# EurocardPowerSupply_mods.net
KiCad netlist of a schematic drawn in EAGLE
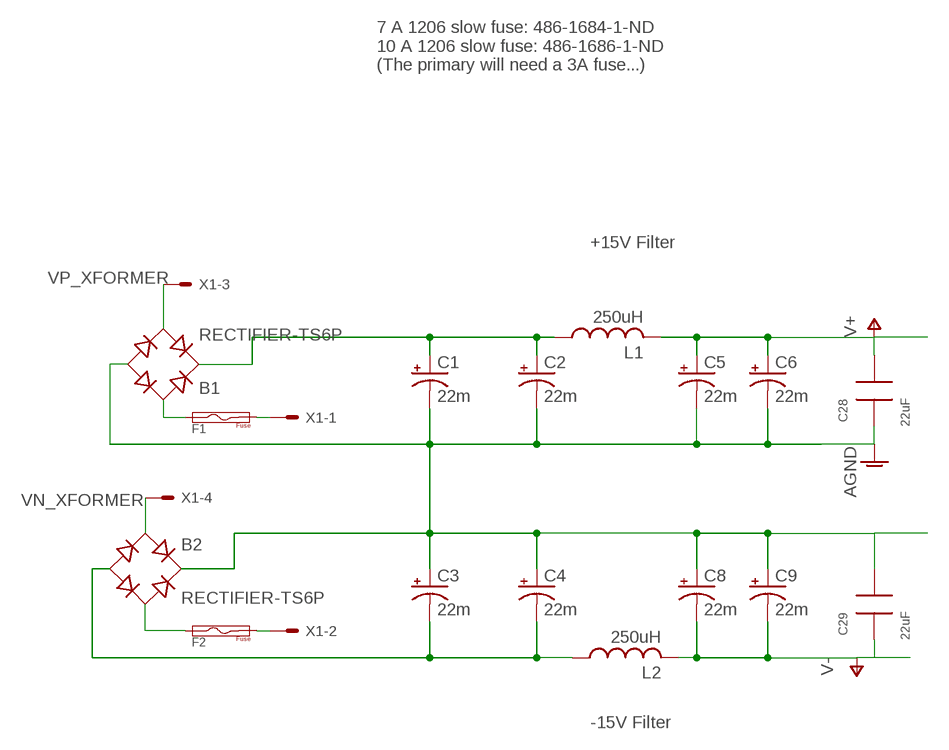
[diagram p0: schematic, sheet 1]
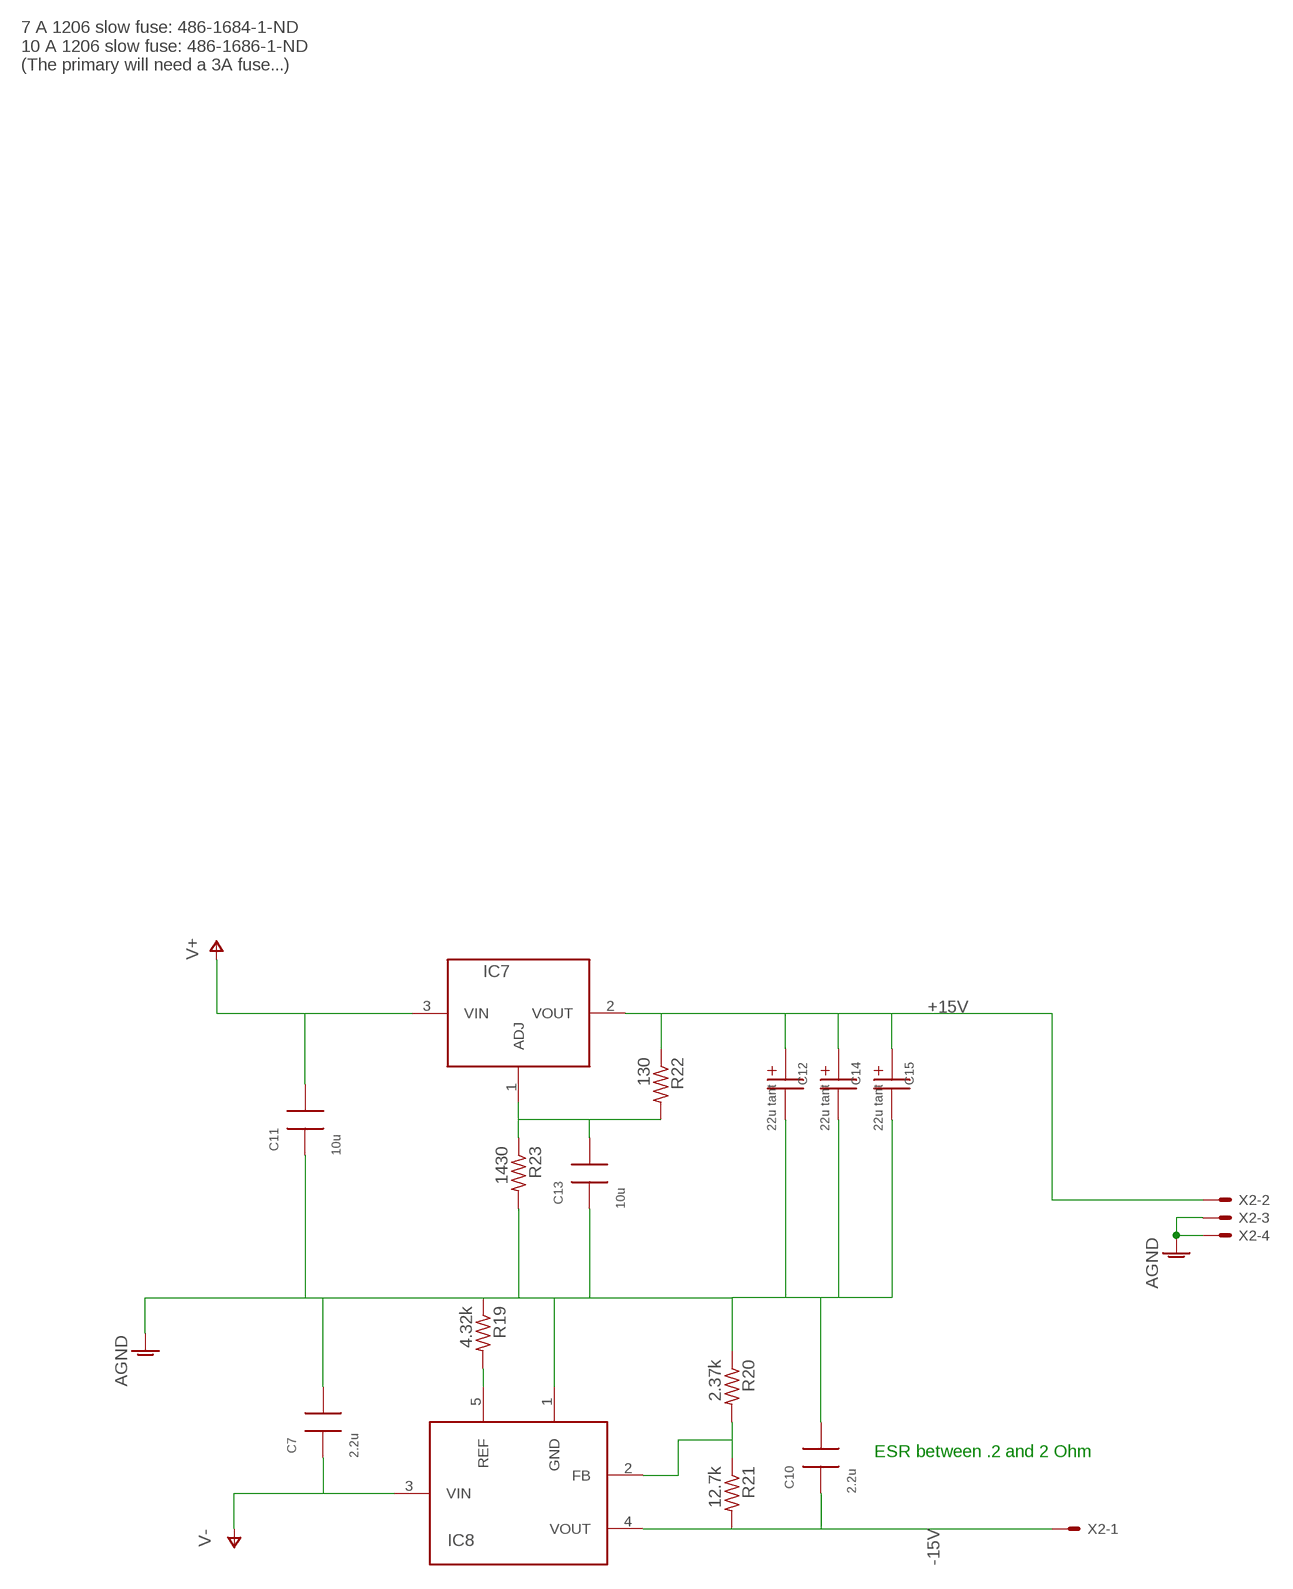
[diagram p1: schematic, sheet 2]
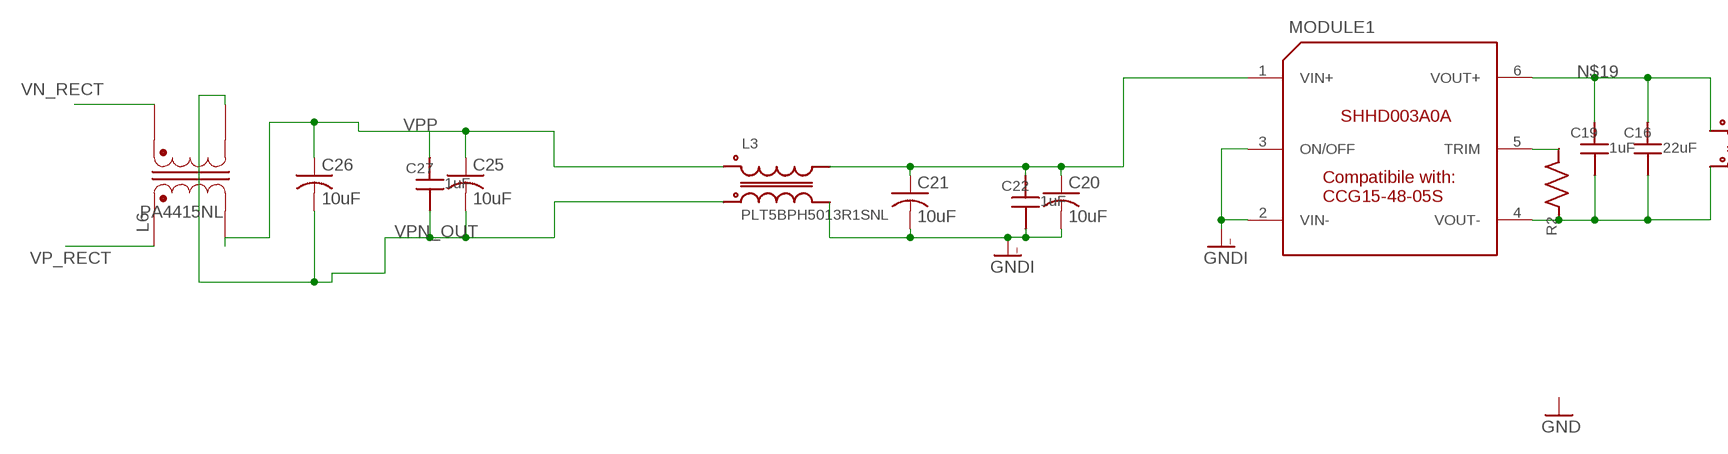
[diagram p2: schematic, sheet 3, part 1 of 2]
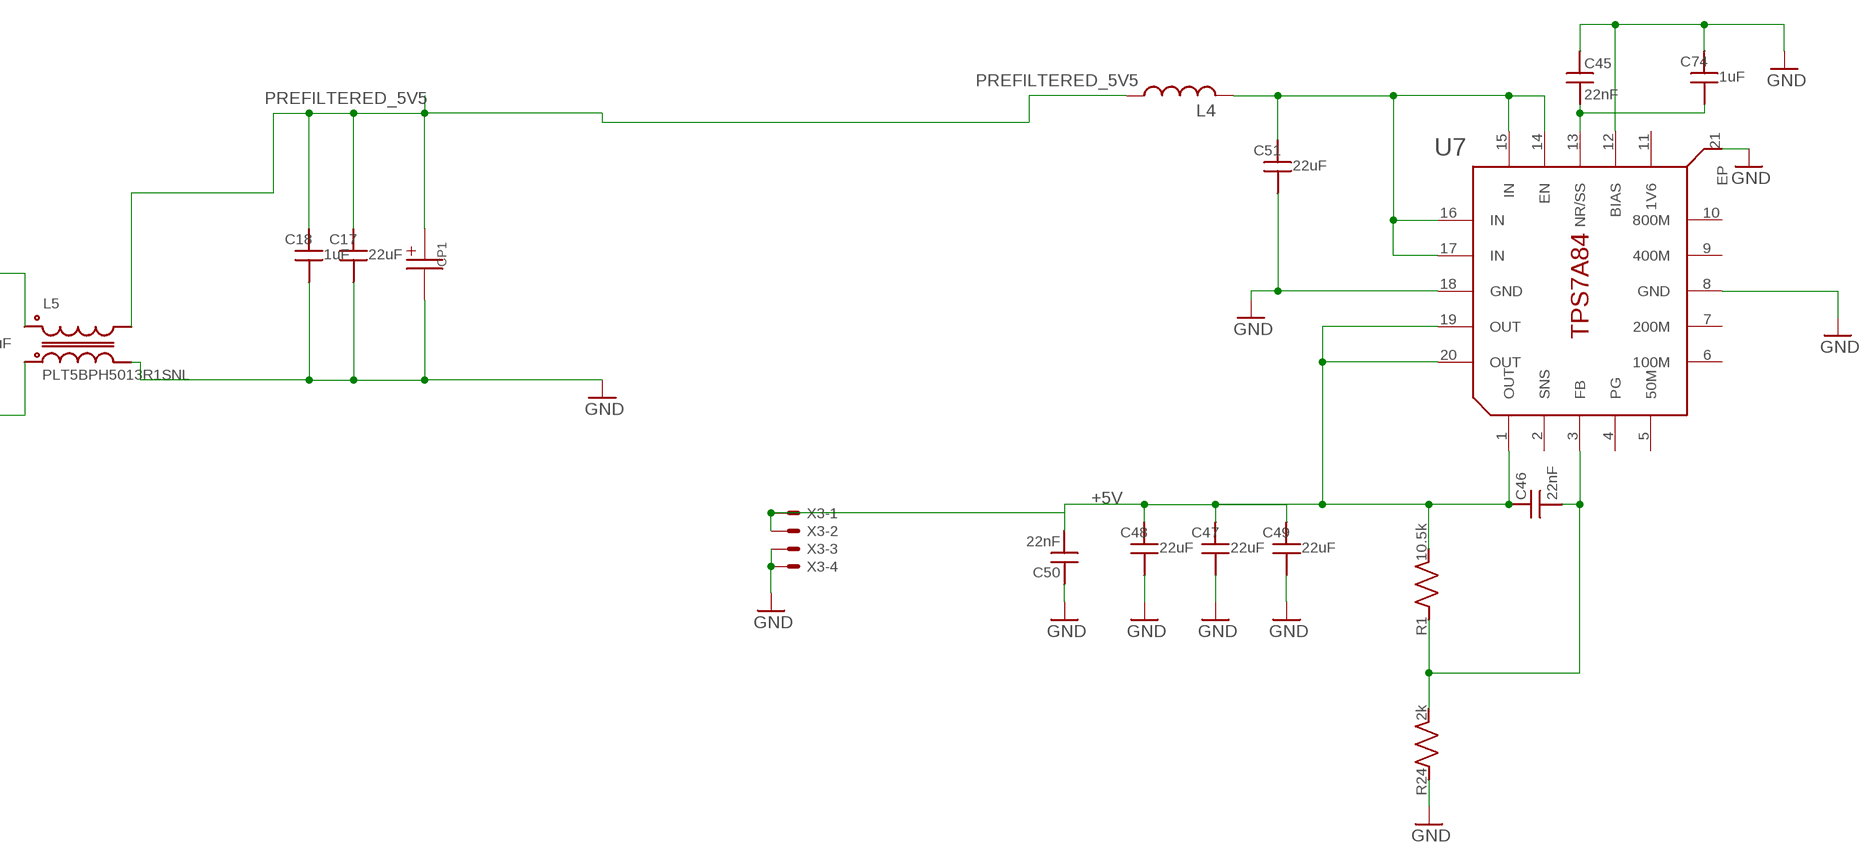
[diagram p3: schematic, sheet 3, part 2 of 2]

(export (version "E")
  (design (tool "Eeschema 10.0.6"))
  (components
    (comp (ref "C7")
      (value "2.2u")
      (footprint "eagle-import:1206")
      (libsource (lib "eagle-import") (part "CAP1206"))
    )
    (comp (ref "C10")
      (value "2.2u")
      (footprint "eagle-import:1206")
      (libsource (lib "eagle-import") (part "CAP1206"))
    )
    (comp (ref "C11")
      (value "10u")
      (footprint "eagle-import:1206")
      (libsource (lib "eagle-import") (part "CAP1206"))
    )
    (comp (ref "C12")
      (value "22u tant")
      (footprint "eagle-import:1206P")
      (libsource (lib "eagle-import") (part "rlc-jqi_CAP-POL1206"))
    )
    (comp (ref "C13")
      (value "10u")
      (footprint "eagle-import:1206")
      (libsource (lib "eagle-import") (part "CAP1206"))
    )
    (comp (ref "C14")
      (value "22u tant")
      (footprint "eagle-import:1206P")
      (libsource (lib "eagle-import") (part "rlc-jqi_CAP-POL1206"))
    )
    (comp (ref "C15")
      (value "22u tant")
      (footprint "eagle-import:1206P")
      (libsource (lib "eagle-import") (part "rlc-jqi_CAP-POL1206"))
    )
    (comp (ref "IC7")
      (value "LM1084TO220")
      (footprint "eagle-import:T03B")
      (libsource (lib "eagle-import") (part "LM1084TO220"))
    )
    (comp (ref "IC8")
      (value "LT1185TO220/INLINE")
      (footprint "eagle-import:T05A")
      (libsource (lib "eagle-import") (part "LT1185TO220/INLINE"))
    )
    (comp (ref "R19")
      (value "4.32k")
      (footprint "eagle-import:R1206")
      (libsource (lib "eagle-import") (part "R-US_R1206"))
    )
    (comp (ref "R20")
      (value "2.37k")
      (footprint "eagle-import:R1206")
      (libsource (lib "eagle-import") (part "R-US_R1206"))
    )
    (comp (ref "R21")
      (value "12.7k")
      (footprint "eagle-import:R1206")
      (libsource (lib "eagle-import") (part "R-US_R1206"))
    )
    (comp (ref "R22")
      (value "130")
      (footprint "eagle-import:R1206")
      (libsource (lib "eagle-import") (part "R-US_R1206"))
    )
    (comp (ref "R23")
      (value "1430")
      (footprint "eagle-import:R1206")
      (libsource (lib "eagle-import") (part "R-US_R1206"))
    )
    (comp (ref "X2")
      (value "5566-4")
      (footprint "eagle-import:5566-4")
      (libsource (lib "eagle-import") (part "5566-4"))
    )
    (comp (ref "B1")
      (value "RECTIFIER-TS6P")
      (footprint "eagle-import:TS6P")
      (libsource (lib "eagle-import") (part "RECTIFIER-TS6P"))
    )
    (comp (ref "B2")
      (value "RECTIFIER-TS6P")
      (footprint "eagle-import:TS6P")
      (libsource (lib "eagle-import") (part "RECTIFIER-TS6P"))
    )
    (comp (ref "C1")
      (value "22m")
      (footprint "eagle-import:EB35D")
      (libsource (lib "eagle-import") (part "CPOL-USEB35D"))
    )
    (comp (ref "C2")
      (value "22m")
      (footprint "eagle-import:EB35D")
      (libsource (lib "eagle-import") (part "CPOL-USEB35D"))
    )
    (comp (ref "C3")
      (value "22m")
      (footprint "eagle-import:EB35D")
      (libsource (lib "eagle-import") (part "CPOL-USEB35D"))
    )
    (comp (ref "C4")
      (value "22m")
      (footprint "eagle-import:EB35D")
      (libsource (lib "eagle-import") (part "CPOL-USEB35D"))
    )
    (comp (ref "C5")
      (value "22m")
      (footprint "eagle-import:EB35D")
      (libsource (lib "eagle-import") (part "CPOL-USEB35D"))
    )
    (comp (ref "C6")
      (value "22m")
      (footprint "eagle-import:EB35D")
      (libsource (lib "eagle-import") (part "CPOL-USEB35D"))
    )
    (comp (ref "C8")
      (value "22m")
      (footprint "eagle-import:EB35D")
      (libsource (lib "eagle-import") (part "CPOL-USEB35D"))
    )
    (comp (ref "C9")
      (value "22m")
      (footprint "eagle-import:EB35D")
      (libsource (lib "eagle-import") (part "CPOL-USEB35D"))
    )
    (comp (ref "C28")
      (value "22uF")
      (footprint "eagle-import:1206")
      (libsource (lib "eagle-import") (part "CAP1206"))
    )
    (comp (ref "C29")
      (value "22uF")
      (footprint "eagle-import:1206")
      (libsource (lib "eagle-import") (part "CAP1206"))
    )
    (comp (ref "F1")
      (value "FUSE1206")
      (footprint "eagle-import:FUSE1206")
      (libsource (lib "eagle-import") (part "FUSE1206"))
    )
    (comp (ref "F2")
      (value "FUSE1206")
      (footprint "eagle-import:FUSE1206")
      (libsource (lib "eagle-import") (part "FUSE1206"))
    )
    (comp (ref "L1")
      (value "250uH")
      (footprint "eagle-import:5721-RC")
      (libsource (lib "eagle-import") (part "INDUCTOR5721-RC"))
    )
    (comp (ref "L2")
      (value "250uH")
      (footprint "eagle-import:5721-RC")
      (libsource (lib "eagle-import") (part "INDUCTOR5721-RC"))
    )
    (comp (ref "X1")
      (value "5566-4")
      (footprint "eagle-import:5566-4")
      (libsource (lib "eagle-import") (part "5566-4"))
    )
    (comp (ref "C16")
      (value "22uF")
      (footprint "eagle-import:C_MLCC_0805")
      (libsource (lib "eagle-import") (part "C_MLCC_SMDCMLCC_0805"))
    )
    (comp (ref "C17")
      (value "22uF")
      (footprint "eagle-import:C_MLCC_0805")
      (libsource (lib "eagle-import") (part "C_MLCC_SMDCMLCC_0805"))
    )
    (comp (ref "C18")
      (value "1uF")
      (footprint "eagle-import:C_MLCC_0805")
      (libsource (lib "eagle-import") (part "C_MLCC_SMDCMLCC_0805"))
    )
    (comp (ref "C19")
      (value "1uF")
      (footprint "eagle-import:C_MLCC_0805")
      (libsource (lib "eagle-import") (part "C_MLCC_SMDCMLCC_0805"))
    )
    (comp (ref "C20")
      (value "10uF")
      (footprint "eagle-import:C2220K")
      (libsource (lib "eagle-import") (part "C-USC2220K"))
    )
    (comp (ref "C21")
      (value "10uF")
      (footprint "eagle-import:C2220K")
      (libsource (lib "eagle-import") (part "C-USC2220K"))
    )
    (comp (ref "C22")
      (value "1uF")
      (footprint "eagle-import:C_MLCC_0805")
      (libsource (lib "eagle-import") (part "C_MLCC_SMDCMLCC_0805"))
    )
    (comp (ref "C25")
      (value "10uF")
      (footprint "eagle-import:C2220K")
      (libsource (lib "eagle-import") (part "C-USC2220K"))
    )
    (comp (ref "C26")
      (value "10uF")
      (footprint "eagle-import:C2220K")
      (libsource (lib "eagle-import") (part "C-USC2220K"))
    )
    (comp (ref "C27")
      (value "1uF")
      (footprint "eagle-import:C_MLCC_0805")
      (libsource (lib "eagle-import") (part "C_MLCC_SMDCMLCC_0805"))
    )
    (comp (ref "C45")
      (value "22nF")
      (footprint "eagle-import:C_MLCC_0306")
      (libsource (lib "eagle-import") (part "C_MLCC_SMDCMLCC_0306"))
    )
    (comp (ref "C46")
      (value "22nF")
      (footprint "eagle-import:C_MLCC_0306")
      (libsource (lib "eagle-import") (part "C_MLCC_SMDCMLCC_0306"))
    )
    (comp (ref "C47")
      (value "22uF")
      (footprint "eagle-import:C_MLCC_0805")
      (libsource (lib "eagle-import") (part "C_MLCC_SMDCMLCC_0805"))
    )
    (comp (ref "C48")
      (value "22uF")
      (footprint "eagle-import:C_MLCC_0805")
      (libsource (lib "eagle-import") (part "C_MLCC_SMDCMLCC_0805"))
    )
    (comp (ref "C49")
      (value "22uF")
      (footprint "eagle-import:C_MLCC_0805")
      (libsource (lib "eagle-import") (part "C_MLCC_SMDCMLCC_0805"))
    )
    (comp (ref "C50")
      (value "22nF")
      (footprint "eagle-import:C_MLCC_0306")
      (libsource (lib "eagle-import") (part "C_MLCC_SMDCMLCC_0306"))
    )
    (comp (ref "C51")
      (value "22uF")
      (footprint "eagle-import:C_MLCC_0805")
      (libsource (lib "eagle-import") (part "C_MLCC_SMDCMLCC_0805"))
    )
    (comp (ref "C74")
      (value "1uF")
      (footprint "eagle-import:C_MLCC_0805")
      (libsource (lib "eagle-import") (part "C_MLCC_SMDCMLCC_0805"))
    )
    (comp (ref "CP1")
      (value "CAP-POLPANASONIC_F")
      (footprint "eagle-import:PANASONIC_F")
      (libsource (lib "eagle-import") (part "CAP-POLPANASONIC_F"))
    )
    (comp (ref "L3")
      (value "PLT5BPH5013R1SNL")
      (footprint "eagle-import:MURATA_CM_CHOKE_PLT5BPH_SERIES")
      (libsource (lib "eagle-import") (part "MURATA_CM_COIL_SERIES_PLT5BPH"))
    )
    (comp (ref "L4")
      (value "MURATA_NFZ5BBW100LN10L")
      (footprint "eagle-import:MURATA_1MHZ_3A_FERRITE")
      (libsource (lib "eagle-import") (part "MURATA_NFZ5BBW100LN10L"))
    )
    (comp (ref "L5")
      (value "PLT5BPH5013R1SNL")
      (footprint "eagle-import:MURATA_CM_CHOKE_PLT5BPH_SERIES")
      (libsource (lib "eagle-import") (part "MURATA_CM_COIL_SERIES_PLT5BPH"))
    )
    (comp (ref "L6")
      (value "PA4415NL")
      (footprint "eagle-import:PA4415NL")
      (libsource (lib "eagle-import") (part "PA4415NL"))
    )
    (comp (ref "MODULE1")
      (value "GE_SHHD003A0A")
      (footprint "eagle-import:GE_SHHD003A0A_THROUGH_HOLE")
      (libsource (lib "eagle-import") (part "GE_SHHD003A0A"))
    )
    (comp (ref "R1")
      (value "10.5k")
      (footprint "eagle-import:R_0805")
      (libsource (lib "eagle-import") (part "R_SMDR0805"))
    )
    (comp (ref "R2")
      (value "R_SMDR0805")
      (footprint "eagle-import:R_0805")
      (libsource (lib "eagle-import") (part "R_SMDR0805"))
    )
    (comp (ref "R24")
      (value "2k")
      (footprint "eagle-import:R_0805")
      (libsource (lib "eagle-import") (part "R_SMDR0805"))
    )
    (comp (ref "U7")
      (value "TEXAS_INSTRUMENTS_TPS7A84")
      (footprint "eagle-import:S-PVQFN-N20")
      (libsource (lib "eagle-import") (part "TEXAS_INSTRUMENTS_TPS7A84"))
    )
    (comp (ref "X3")
      (value "5566-4")
      (footprint "eagle-import:5566-4")
      (libsource (lib "eagle-import") (part "5566-4"))
    )
  )
  (nets
    (net (code "1") (name "+5V") (class "Default")
      (node (ref "C46") (pin "P$1") (pinfunction "1_P$1") (pintype "passive"))
      (node (ref "C47") (pin "P$1") (pinfunction "1_P$1") (pintype "passive"))
      (node (ref "C48") (pin "P$1") (pinfunction "1_P$1") (pintype "passive"))
      (node (ref "C49") (pin "P$1") (pinfunction "1_P$1") (pintype "passive"))
      (node (ref "C50") (pin "P$2") (pinfunction "2_P$2") (pintype "passive"))
      (node (ref "R1") (pin "P$2") (pinfunction "2_P$2") (pintype "passive"))
      (node (ref "U7") (pin "1") (pinfunction "OUT_1") (pintype "bidirectional"))
      (node (ref "U7") (pin "19") (pinfunction "OUT_19") (pintype "bidirectional"))
      (node (ref "U7") (pin "20") (pinfunction "OUT_20") (pintype "bidirectional"))
      (node (ref "X3") (pin "1") (pinfunction "S_1") (pintype "passive"))
      (node (ref "X3") (pin "2") (pinfunction "S_2") (pintype "passive"))
    )
    (net (code "2") (name "+15V") (class "Default")
      (node (ref "C12") (pin "1") (pinfunction "P$1_1") (pintype "passive"))
      (node (ref "C14") (pin "1") (pinfunction "P$1_1") (pintype "passive"))
      (node (ref "C15") (pin "1") (pinfunction "P$1_1") (pintype "passive"))
      (node (ref "IC7") (pin "2") (pinfunction "VOUT_2") (pintype "bidirectional"))
      (node (ref "R22") (pin "1") (pinfunction "1_1") (pintype "passive"))
      (node (ref "X2") (pin "2") (pinfunction "S_2") (pintype "passive"))
    )
    (net (code "3") (name "-15V") (class "Default")
      (node (ref "C10") (pin "1") (pinfunction "P$1_1") (pintype "passive"))
      (node (ref "IC8") (pin "4") (pinfunction "VOUT_4") (pintype "bidirectional"))
      (node (ref "R21") (pin "2") (pinfunction "2_2") (pintype "passive"))
      (node (ref "X2") (pin "1") (pinfunction "S_1") (pintype "passive"))
    )
    (net (code "4") (name "AGND") (class "Default")
      (node (ref "B1") (pin "-") (pinfunction "-_-") (pintype "passive"))
      (node (ref "B2") (pin "+") (pinfunction "+_+") (pintype "passive"))
      (node (ref "C1") (pin "-") (pinfunction "-_-") (pintype "passive"))
      (node (ref "C10") (pin "2") (pinfunction "P$2_2") (pintype "passive"))
      (node (ref "C11") (pin "1") (pinfunction "P$1_1") (pintype "passive"))
      (node (ref "C12") (pin "2") (pinfunction "P$2_2") (pintype "passive"))
      (node (ref "C13") (pin "1") (pinfunction "P$1_1") (pintype "passive"))
      (node (ref "C14") (pin "2") (pinfunction "P$2_2") (pintype "passive"))
      (node (ref "C15") (pin "2") (pinfunction "P$2_2") (pintype "passive"))
      (node (ref "C2") (pin "-") (pinfunction "-_-") (pintype "passive"))
      (node (ref "C28") (pin "1") (pinfunction "P$1_1") (pintype "passive"))
      (node (ref "C29") (pin "2") (pinfunction "P$2_2") (pintype "passive"))
      (node (ref "C3") (pin "+") (pinfunction "+_+") (pintype "passive"))
      (node (ref "C4") (pin "+") (pinfunction "+_+") (pintype "passive"))
      (node (ref "C5") (pin "-") (pinfunction "-_-") (pintype "passive"))
      (node (ref "C6") (pin "-") (pinfunction "-_-") (pintype "passive"))
      (node (ref "C7") (pin "2") (pinfunction "P$2_2") (pintype "passive"))
      (node (ref "C8") (pin "+") (pinfunction "+_+") (pintype "passive"))
      (node (ref "C9") (pin "+") (pinfunction "+_+") (pintype "passive"))
      (node (ref "IC8") (pin "1") (pinfunction "GND_1") (pintype "bidirectional"))
      (node (ref "R19") (pin "1") (pinfunction "1_1") (pintype "passive"))
      (node (ref "R20") (pin "1") (pinfunction "1_1") (pintype "passive"))
      (node (ref "R23") (pin "2") (pinfunction "2_2") (pintype "passive"))
      (node (ref "X2") (pin "3") (pinfunction "S_3") (pintype "passive"))
      (node (ref "X2") (pin "4") (pinfunction "S_4") (pintype "passive"))
    )
    (net (code "5") (name "GND") (class "Default")
      (node (ref "C17") (pin "P$2") (pinfunction "2_P$2") (pintype "passive"))
      (node (ref "C18") (pin "P$2") (pinfunction "2_P$2") (pintype "passive"))
      (node (ref "C45") (pin "P$1") (pinfunction "1_P$1") (pintype "passive"))
      (node (ref "C47") (pin "P$2") (pinfunction "2_P$2") (pintype "passive"))
      (node (ref "C48") (pin "P$2") (pinfunction "2_P$2") (pintype "passive"))
      (node (ref "C49") (pin "P$2") (pinfunction "2_P$2") (pintype "passive"))
      (node (ref "C50") (pin "P$1") (pinfunction "1_P$1") (pintype "passive"))
      (node (ref "C51") (pin "P$2") (pinfunction "2_P$2") (pintype "passive"))
      (node (ref "C74") (pin "P$1") (pinfunction "1_P$1") (pintype "passive"))
      (node (ref "CP1") (pin "-") (pinfunction "P$2_-") (pintype "passive"))
      (node (ref "L5") (pin "P$3") (pinfunction "3_P$3") (pintype "passive"))
      (node (ref "R24") (pin "P$1") (pinfunction "1_P$1") (pintype "passive"))
      (node (ref "U7") (pin "12") (pinfunction "BIAS_12") (pintype "bidirectional"))
      (node (ref "U7") (pin "18") (pinfunction "GND_18") (pintype "bidirectional"))
      (node (ref "U7") (pin "21") (pinfunction "EP_21") (pintype "bidirectional"))
      (node (ref "U7") (pin "8") (pinfunction "GND_8") (pintype "bidirectional"))
      (node (ref "X3") (pin "3") (pinfunction "S_3") (pintype "passive"))
      (node (ref "X3") (pin "4") (pinfunction "S_4") (pintype "passive"))
    )
    (net (code "6") (name "GNDI") (class "Default")
      (node (ref "C20") (pin "2") (pinfunction "2_2") (pintype "passive"))
      (node (ref "C21") (pin "2") (pinfunction "2_2") (pintype "passive"))
      (node (ref "C22") (pin "P$2") (pinfunction "2_P$2") (pintype "passive"))
      (node (ref "L3") (pin "P$3") (pinfunction "3_P$3") (pintype "passive"))
      (node (ref "MODULE1") (pin "2") (pinfunction "VIN-_2") (pintype "bidirectional"))
      (node (ref "MODULE1") (pin "3") (pinfunction "ON/OFF_3") (pintype "bidirectional"))
    )
    (net (code "7") (name "N$19") (class "Default")
      (node (ref "C16") (pin "P$1") (pinfunction "1_P$1") (pintype "passive"))
      (node (ref "C19") (pin "P$1") (pinfunction "1_P$1") (pintype "passive"))
      (node (ref "L5") (pin "P$1") (pinfunction "2_P$1") (pintype "passive"))
      (node (ref "MODULE1") (pin "6") (pinfunction "VOUT+_6") (pintype "bidirectional"))
    )
    (net (code "8") (name "Net-(C13-P$2)") (class "Default")
      (node (ref "C13") (pin "2") (pinfunction "P$2_2") (pintype "passive"))
      (node (ref "IC7") (pin "1") (pinfunction "ADJ_1") (pintype "bidirectional"))
      (node (ref "R22") (pin "2") (pinfunction "2_2") (pintype "passive"))
      (node (ref "R23") (pin "1") (pinfunction "1_1") (pintype "passive"))
    )
    (net (code "9") (name "Net-(C16-2)") (class "Default")
      (node (ref "C16") (pin "P$2") (pinfunction "2_P$2") (pintype "passive"))
      (node (ref "C19") (pin "P$2") (pinfunction "2_P$2") (pintype "passive"))
      (node (ref "L5") (pin "P$4") (pinfunction "1_P$4") (pintype "passive"))
      (node (ref "MODULE1") (pin "4") (pinfunction "VOUT-_4") (pintype "bidirectional"))
      (node (ref "R2") (pin "P$1") (pinfunction "1_P$1") (pintype "passive"))
    )
    (net (code "10") (name "Net-(C22-1)") (class "Default")
      (node (ref "C20") (pin "1") (pinfunction "1_1") (pintype "passive"))
      (node (ref "C21") (pin "1") (pinfunction "1_1") (pintype "passive"))
      (node (ref "C22") (pin "P$1") (pinfunction "1_P$1") (pintype "passive"))
      (node (ref "L3") (pin "P$2") (pinfunction "4_P$2") (pintype "passive"))
      (node (ref "MODULE1") (pin "1") (pinfunction "VIN+_1") (pintype "bidirectional"))
    )
    (net (code "11") (name "Net-(C45-2)") (class "Default")
      (node (ref "C45") (pin "P$2") (pinfunction "2_P$2") (pintype "passive"))
      (node (ref "C74") (pin "P$2") (pinfunction "2_P$2") (pintype "passive"))
      (node (ref "U7") (pin "13") (pinfunction "NR/SS_13") (pintype "bidirectional"))
    )
    (net (code "12") (name "Net-(C46-2)") (class "Default")
      (node (ref "C46") (pin "P$2") (pinfunction "2_P$2") (pintype "passive"))
      (node (ref "R1") (pin "P$1") (pinfunction "1_P$1") (pintype "passive"))
      (node (ref "R24") (pin "P$2") (pinfunction "2_P$2") (pintype "passive"))
      (node (ref "U7") (pin "3") (pinfunction "FB_3") (pintype "bidirectional"))
    )
    (net (code "13") (name "Net-(C51-1)") (class "Default")
      (node (ref "C51") (pin "P$1") (pinfunction "1_P$1") (pintype "passive"))
      (node (ref "L4") (pin "P$2") (pinfunction "2_P$2") (pintype "passive"))
      (node (ref "U7") (pin "14") (pinfunction "EN_14") (pintype "bidirectional"))
      (node (ref "U7") (pin "15") (pinfunction "IN_15") (pintype "bidirectional"))
      (node (ref "U7") (pin "16") (pinfunction "IN_16") (pintype "bidirectional"))
      (node (ref "U7") (pin "17") (pinfunction "IN_17") (pintype "bidirectional"))
    )
    (net (code "14") (name "Net-(F1-P$1)") (class "Default")
      (node (ref "B1") (pin "AC1") (pinfunction "AC1_AC1") (pintype "passive"))
      (node (ref "F1") (pin "1") (pinfunction "P$1_1") (pintype "bidirectional"))
    )
    (net (code "15") (name "Net-(F1-P$2)") (class "Default")
      (node (ref "F1") (pin "2") (pinfunction "P$2_2") (pintype "bidirectional"))
      (node (ref "X1") (pin "1") (pinfunction "S_1") (pintype "passive"))
    )
    (net (code "16") (name "Net-(F2-P$1)") (class "Default")
      (node (ref "B2") (pin "AC2") (pinfunction "AC2_AC2") (pintype "passive"))
      (node (ref "F2") (pin "1") (pinfunction "P$1_1") (pintype "bidirectional"))
    )
    (net (code "17") (name "Net-(F2-P$2)") (class "Default")
      (node (ref "F2") (pin "2") (pinfunction "P$2_2") (pintype "bidirectional"))
      (node (ref "X1") (pin "2") (pinfunction "S_2") (pintype "passive"))
    )
    (net (code "18") (name "Net-(IC8-FB)") (class "Default")
      (node (ref "IC8") (pin "2") (pinfunction "FB_2") (pintype "bidirectional"))
      (node (ref "R20") (pin "2") (pinfunction "2_2") (pintype "passive"))
      (node (ref "R21") (pin "1") (pinfunction "1_1") (pintype "passive"))
    )
    (net (code "19") (name "Net-(IC8-REF)") (class "Default")
      (node (ref "IC8") (pin "5") (pinfunction "REF_5") (pintype "bidirectional"))
      (node (ref "R19") (pin "2") (pinfunction "2_2") (pintype "passive"))
    )
    (net (code "20") (name "Net-(MODULE1-TRIM)") (class "Default")
      (node (ref "MODULE1") (pin "5") (pinfunction "TRIM_5") (pintype "bidirectional"))
      (node (ref "R2") (pin "P$2") (pinfunction "2_P$2") (pintype "passive"))
    )
    (net (code "21") (name "PREFILTERED_5V5") (class "Default")
      (node (ref "C17") (pin "P$1") (pinfunction "1_P$1") (pintype "passive"))
      (node (ref "C18") (pin "P$1") (pinfunction "1_P$1") (pintype "passive"))
      (node (ref "CP1") (pin "+") (pinfunction "P$1_+") (pintype "passive"))
      (node (ref "L4") (pin "P$1") (pinfunction "1_P$1") (pintype "passive"))
      (node (ref "L5") (pin "P$2") (pinfunction "4_P$2") (pintype "passive"))
    )
    (net (code "22") (name "V+") (class "Default")
      (node (ref "C11") (pin "2") (pinfunction "P$2_2") (pintype "passive"))
      (node (ref "C28") (pin "2") (pinfunction "P$2_2") (pintype "passive"))
      (node (ref "C5") (pin "+") (pinfunction "+_+") (pintype "passive"))
      (node (ref "C6") (pin "+") (pinfunction "+_+") (pintype "passive"))
      (node (ref "IC7") (pin "3") (pinfunction "VIN_3") (pintype "bidirectional"))
      (node (ref "L1") (pin "P$2") (pinfunction "2_P$2") (pintype "passive"))
    )
    (net (code "23") (name "V-") (class "Default")
      (node (ref "C29") (pin "1") (pinfunction "P$1_1") (pintype "passive"))
      (node (ref "C7") (pin "1") (pinfunction "P$1_1") (pintype "passive"))
      (node (ref "C8") (pin "-") (pinfunction "-_-") (pintype "passive"))
      (node (ref "C9") (pin "-") (pinfunction "-_-") (pintype "passive"))
      (node (ref "IC8") (pin "3") (pinfunction "VIN_3") (pintype "bidirectional"))
      (node (ref "L2") (pin "P$2") (pinfunction "2_P$2") (pintype "passive"))
    )
    (net (code "24") (name "VN_RECT") (class "Default")
      (node (ref "B2") (pin "-") (pinfunction "-_-") (pintype "passive"))
      (node (ref "C3") (pin "-") (pinfunction "-_-") (pintype "passive"))
      (node (ref "C4") (pin "-") (pinfunction "-_-") (pintype "passive"))
      (node (ref "L2") (pin "P$1") (pinfunction "1_P$1") (pintype "passive"))
      (node (ref "L6") (pin "2") (pinfunction "2_2") (pintype "bidirectional"))
    )
    (net (code "25") (name "VN_XFORMER") (class "Default")
      (node (ref "B2") (pin "AC1") (pinfunction "AC1_AC1") (pintype "passive"))
      (node (ref "X1") (pin "4") (pinfunction "S_4") (pintype "passive"))
    )
    (net (code "26") (name "VPN_OUT") (class "Default")
      (node (ref "C25") (pin "2") (pinfunction "2_2") (pintype "passive"))
      (node (ref "C26") (pin "2") (pinfunction "2_2") (pintype "passive"))
      (node (ref "C27") (pin "P$2") (pinfunction "2_P$2") (pintype "passive"))
      (node (ref "L3") (pin "P$4") (pinfunction "1_P$4") (pintype "passive"))
      (node (ref "L6") (pin "3") (pinfunction "4_3") (pintype "bidirectional"))
    )
    (net (code "27") (name "VPP") (class "Default")
      (node (ref "C25") (pin "1") (pinfunction "1_1") (pintype "passive"))
      (node (ref "C26") (pin "1") (pinfunction "1_1") (pintype "passive"))
      (node (ref "C27") (pin "P$1") (pinfunction "1_P$1") (pintype "passive"))
      (node (ref "L3") (pin "P$1") (pinfunction "2_P$1") (pintype "passive"))
      (node (ref "L6") (pin "4") (pinfunction "3_4") (pintype "bidirectional"))
    )
    (net (code "28") (name "VP_RECT") (class "Default")
      (node (ref "B1") (pin "+") (pinfunction "+_+") (pintype "passive"))
      (node (ref "C1") (pin "+") (pinfunction "+_+") (pintype "passive"))
      (node (ref "C2") (pin "+") (pinfunction "+_+") (pintype "passive"))
      (node (ref "L1") (pin "P$1") (pinfunction "1_P$1") (pintype "passive"))
      (node (ref "L6") (pin "1") (pinfunction "1_1") (pintype "bidirectional"))
    )
    (net (code "29") (name "VP_XFORMER") (class "Default")
      (node (ref "B1") (pin "AC2") (pinfunction "AC2_AC2") (pintype "passive"))
      (node (ref "X1") (pin "3") (pinfunction "S_3") (pintype "passive"))
    )
    (net (code "30") (name "unconnected-(U7-1V6-Pad11)") (class "Default")
      (node (ref "U7") (pin "11") (pinfunction "1V6_11") (pintype "bidirectional"))
    )
    (net (code "31") (name "unconnected-(U7-50M-Pad5)") (class "Default")
      (node (ref "U7") (pin "5") (pinfunction "50M_5") (pintype "bidirectional"))
    )
    (net (code "32") (name "unconnected-(U7-100M-Pad6)") (class "Default")
      (node (ref "U7") (pin "6") (pinfunction "100M_6") (pintype "bidirectional"))
    )
    (net (code "33") (name "unconnected-(U7-200M-Pad7)") (class "Default")
      (node (ref "U7") (pin "7") (pinfunction "200M_7") (pintype "bidirectional"))
    )
    (net (code "34") (name "unconnected-(U7-400M-Pad9)") (class "Default")
      (node (ref "U7") (pin "9") (pinfunction "400M_9") (pintype "bidirectional"))
    )
    (net (code "35") (name "unconnected-(U7-800M-Pad10)") (class "Default")
      (node (ref "U7") (pin "10") (pinfunction "800M_10") (pintype "bidirectional"))
    )
    (net (code "36") (name "unconnected-(U7-PG-Pad4)") (class "Default")
      (node (ref "U7") (pin "4") (pinfunction "PG_4") (pintype "bidirectional"))
    )
    (net (code "37") (name "unconnected-(U7-SNS-Pad2)") (class "Default")
      (node (ref "U7") (pin "2") (pinfunction "SNS_2") (pintype "bidirectional"))
    )
  )
)
